# breakout_board.net
KiCad netlist of a schematic drawn in EAGLE
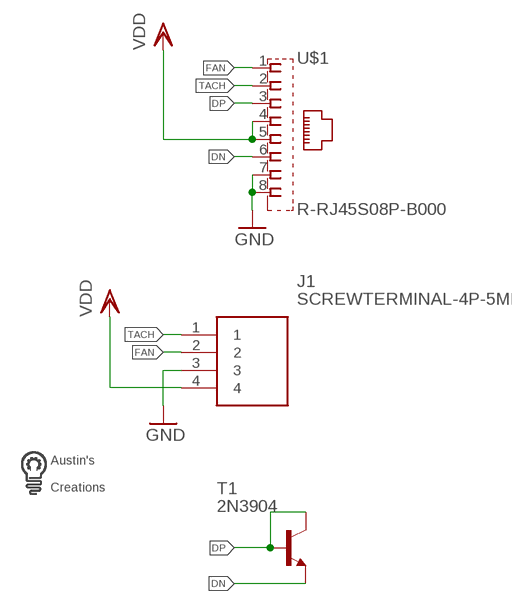
[diagram p0: schematic, sheet 1]

(export (version "E")
  (design (tool "Eeschema 10.0.6"))
  (components
    (comp (ref "J1")
      (value "SCREWTERMINAL-4P-5MM")
      (footprint "eagle-import:SCREWTERMINAL-4P-5MM")
      (fields
        (field (name "MANUFACTURER_PART_NUMBER") "TB001-500-04BE")
        (field (name "MOUSER_PART_NUMBER") "490-TB001-500-04BE")
      )
      (libsource (lib "eagle-import") (part "SCREWTERMINAL-4P-5MM"))
    )
    (comp (ref "T1")
      (value "2N3904")
      (footprint "eagle-import:TO92")
      (libsource (lib "eagle-import") (part "2N3904"))
    )
    (comp (ref "U$1")
      (value "R-RJ45S08P-B000")
      (footprint "eagle-import:R-RJ45S08P-B000")
      (libsource (lib "eagle-import") (part "R-RJ45S08P-B000"))
    )
    (comp (ref "U$2")
      (value "LOGOMED")
      (footprint "eagle-import:LOGOMED")
      (libsource (lib "eagle-import") (part "LOGOMED"))
    )
  )
  (nets
    (net (code "1") (name "DN") (class "Default")
      (node (ref "T1") (pin "3") (pinfunction "E_3") (pintype "passive"))
      (node (ref "U$1") (pin "6") (pinfunction "6_6") (pintype "passive"))
    )
    (net (code "2") (name "DP") (class "Default")
      (node (ref "T1") (pin "1") (pinfunction "C_1") (pintype "passive"))
      (node (ref "T1") (pin "2") (pinfunction "B_2") (pintype "passive"))
      (node (ref "U$1") (pin "3") (pinfunction "3_3") (pintype "passive"))
    )
    (net (code "3") (name "FAN") (class "Default")
      (node (ref "J1") (pin "2") (pinfunction "2_2") (pintype "bidirectional"))
      (node (ref "U$1") (pin "1") (pinfunction "1_1") (pintype "passive"))
    )
    (net (code "4") (name "GND") (class "Default")
      (node (ref "J1") (pin "3") (pinfunction "3_3") (pintype "bidirectional"))
      (node (ref "U$1") (pin "7") (pinfunction "7_7") (pintype "passive"))
      (node (ref "U$1") (pin "8") (pinfunction "8_8") (pintype "passive"))
    )
    (net (code "5") (name "TACH") (class "Default")
      (node (ref "J1") (pin "1") (pinfunction "1_1") (pintype "bidirectional"))
      (node (ref "U$1") (pin "2") (pinfunction "2_2") (pintype "passive"))
    )
    (net (code "6") (name "VDD") (class "Default")
      (node (ref "J1") (pin "4") (pinfunction "4_4") (pintype "bidirectional"))
      (node (ref "U$1") (pin "4") (pinfunction "4_4") (pintype "passive"))
      (node (ref "U$1") (pin "5") (pinfunction "5_5") (pintype "passive"))
    )
  )
)
